# WS2812B_breakout.net
KiCad netlist of a schematic drawn in EAGLE
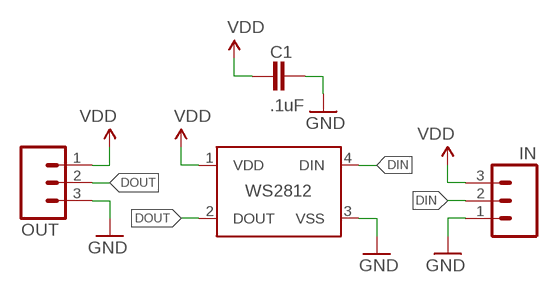
[diagram p0: schematic, sheet 1]

(export (version "E")
  (design (tool "Eeschema 10.0.6"))
  (components
    (comp (ref "C1")
      (value ".1uF")
      (footprint "eagle-import:C805")
      (libsource (lib "eagle-import") (part "CAPACITOR_NPOL-0805"))
    )
    (comp (ref "IN")
      (value "CONN_03LOCK")
      (footprint "eagle-import:1X03_LOCK")
      (libsource (lib "eagle-import") (part "CONN_03LOCK"))
    )
    (comp (ref "OUT")
      (value "CONN_03LOCK")
      (footprint "eagle-import:1X03_LOCK")
      (libsource (lib "eagle-import") (part "CONN_03LOCK"))
    )
    (comp (ref "WS2812")
      (value "WS2812B")
      (footprint "eagle-import:WS2812B")
      (libsource (lib "eagle-import") (part "WS2812B"))
    )
  )
  (nets
    (net (code "1") (name "DIN") (class "Default")
      (node (ref "IN") (pin "2") (pinfunction "2_2") (pintype "passive"))
      (node (ref "WS2812") (pin "4") (pinfunction "DIN_4") (pintype "input"))
    )
    (net (code "2") (name "DOUT") (class "Default")
      (node (ref "OUT") (pin "2") (pinfunction "2_2") (pintype "passive"))
      (node (ref "WS2812") (pin "2") (pinfunction "DOUT_2") (pintype "output"))
    )
    (net (code "3") (name "GND") (class "Default")
      (node (ref "C1") (pin "2") (pinfunction "2_2") (pintype "passive"))
      (node (ref "IN") (pin "1") (pinfunction "1_1") (pintype "passive"))
      (node (ref "OUT") (pin "3") (pinfunction "3_3") (pintype "passive"))
      (node (ref "WS2812") (pin "3") (pinfunction "VSS_3") (pintype "power_in"))
    )
    (net (code "4") (name "VDD") (class "Default")
      (node (ref "C1") (pin "1") (pinfunction "1_1") (pintype "passive"))
      (node (ref "IN") (pin "3") (pinfunction "3_3") (pintype "passive"))
      (node (ref "OUT") (pin "1") (pinfunction "1_1") (pintype "passive"))
      (node (ref "WS2812") (pin "1") (pinfunction "VDD_1") (pintype "power_in"))
    )
  )
)
